# Filter_Board.net
KiCad netlist of a schematic drawn in EAGLE
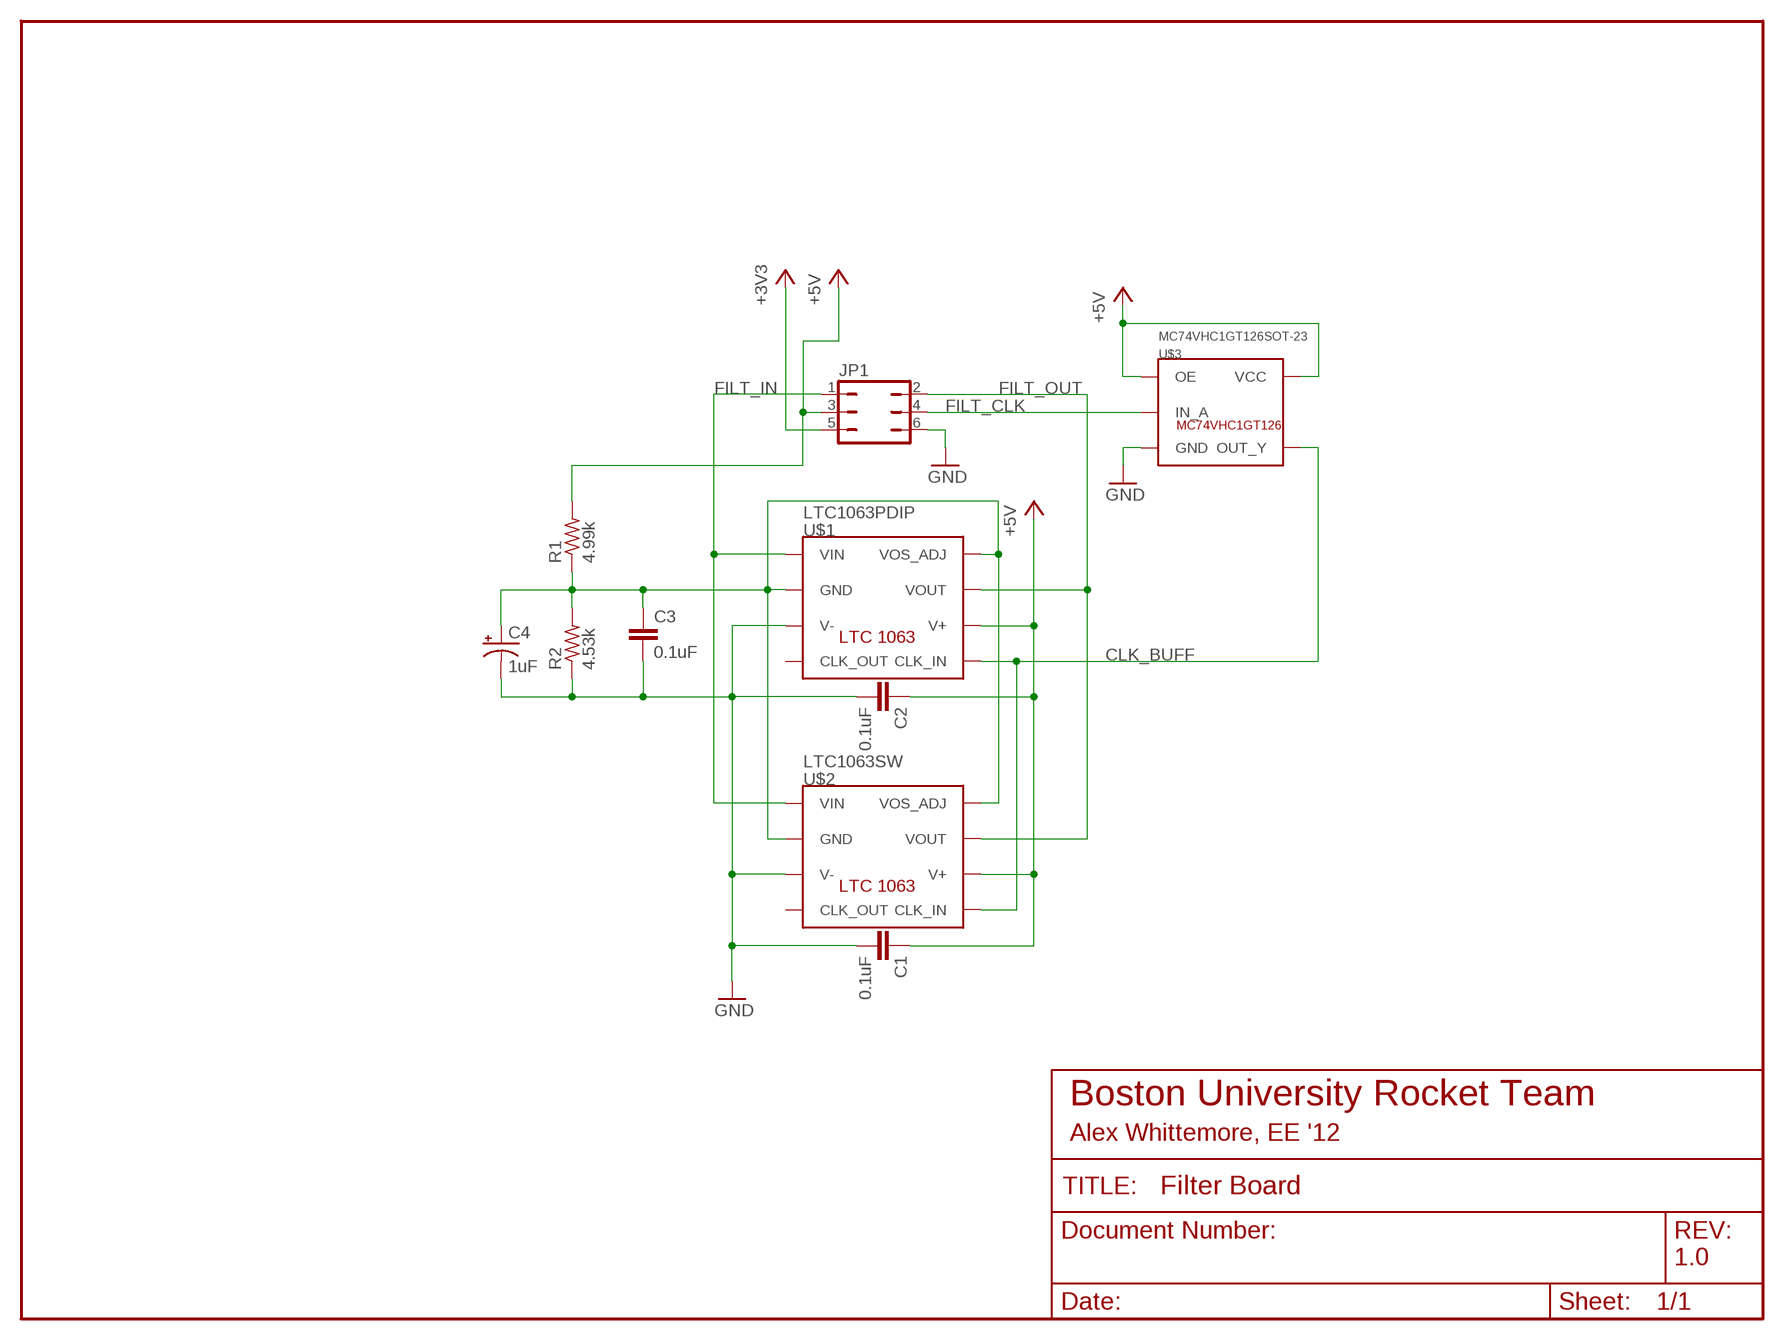
[diagram p0: schematic, sheet 1]

(export (version "E")
  (design (tool "Eeschema 10.0.6"))
  (components
    (comp (ref "C1")
      (value "0.1uF")
      (footprint "eagle-import:0402-CAP")
      (libsource (lib "eagle-import") (part "CAP0402-CAP"))
    )
    (comp (ref "C2")
      (value "0.1uF")
      (footprint "eagle-import:0402-CAP")
      (libsource (lib "eagle-import") (part "CAP0402-CAP"))
    )
    (comp (ref "C3")
      (value "0.1uF")
      (footprint "eagle-import:0402-CAP")
      (libsource (lib "eagle-import") (part "CAP0402-CAP"))
    )
    (comp (ref "C4")
      (value "1uF")
      (footprint "eagle-import:EIA3216")
      (libsource (lib "eagle-import") (part "CAP_POL1206"))
    )
    (comp (ref "JP1")
      (value "JP3Q")
      (footprint "eagle-import:JP3Q")
      (libsource (lib "eagle-import") (part "JP3Q"))
    )
    (comp (ref "R1")
      (value "4.99k")
      (footprint "eagle-import:0207_7")
      (libsource (lib "eagle-import") (part "R-US_0207/7"))
    )
    (comp (ref "R2")
      (value "4.53k")
      (footprint "eagle-import:0207_7")
      (libsource (lib "eagle-import") (part "R-US_0207/7"))
    )
    (comp (ref "U$1")
      (value "LTC1063PDIP")
      (footprint "eagle-import:SOCKED-08")
      (libsource (lib "eagle-import") (part "LTC1063PDIP"))
    )
    (comp (ref "U$2")
      (value "LTC1063SW")
      (footprint "eagle-import:SOP16")
      (libsource (lib "eagle-import") (part "LTC1063SW"))
    )
    (comp (ref "U$3")
      (value "MC74VHC1GT126SOT-23")
      (footprint "eagle-import:SOT23-5L")
      (libsource (lib "eagle-import") (part "MC74VHC1GT126SOT-23"))
    )
  )
  (nets
    (net (code "1") (name "+3V3") (class "Default")
      (node (ref "JP1") (pin "5") (pinfunction "5_5") (pintype "passive"))
    )
    (net (code "2") (name "+5V") (class "Default")
      (node (ref "C1") (pin "1") (pinfunction "1_1") (pintype "passive"))
      (node (ref "C2") (pin "1") (pinfunction "1_1") (pintype "passive"))
      (node (ref "JP1") (pin "3") (pinfunction "3_3") (pintype "passive"))
      (node (ref "R1") (pin "2") (pinfunction "2_2") (pintype "passive"))
      (node (ref "U$1") (pin "6") (pinfunction "V+_6") (pintype "bidirectional"))
      (node (ref "U$2") (pin "12") (pinfunction "V+_12") (pintype "bidirectional"))
      (node (ref "U$3") (pin "1") (pinfunction "OE_1") (pintype "bidirectional"))
      (node (ref "U$3") (pin "5") (pinfunction "VCC_5") (pintype "bidirectional"))
    )
    (net (code "3") (name "/CLK_BUFF") (class "Default")
      (node (ref "U$1") (pin "5") (pinfunction "CLK_IN_5") (pintype "bidirectional"))
      (node (ref "U$2") (pin "9") (pinfunction "CLK_IN_9") (pintype "bidirectional"))
      (node (ref "U$3") (pin "4") (pinfunction "OUT_Y_4") (pintype "bidirectional"))
    )
    (net (code "4") (name "/FILT_CLK") (class "Default")
      (node (ref "JP1") (pin "4") (pinfunction "4_4") (pintype "passive"))
      (node (ref "U$3") (pin "2") (pinfunction "IN_A_2") (pintype "bidirectional"))
    )
    (net (code "5") (name "/FILT_IN") (class "Default")
      (node (ref "JP1") (pin "1") (pinfunction "1_1") (pintype "passive"))
      (node (ref "U$1") (pin "1") (pinfunction "VIN_1") (pintype "bidirectional"))
      (node (ref "U$2") (pin "2") (pinfunction "VIN_2") (pintype "bidirectional"))
    )
    (net (code "6") (name "/FILT_OUT") (class "Default")
      (node (ref "JP1") (pin "2") (pinfunction "2_2") (pintype "passive"))
      (node (ref "U$1") (pin "7") (pinfunction "VOUT_7") (pintype "bidirectional"))
      (node (ref "U$2") (pin "14") (pinfunction "VOUT_14") (pintype "bidirectional"))
    )
    (net (code "7") (name "GND") (class "Default")
      (node (ref "C1") (pin "2") (pinfunction "2_2") (pintype "passive"))
      (node (ref "C2") (pin "2") (pinfunction "2_2") (pintype "passive"))
      (node (ref "C3") (pin "2") (pinfunction "2_2") (pintype "passive"))
      (node (ref "C4") (pin "C") (pinfunction "-_C") (pintype "passive"))
      (node (ref "JP1") (pin "6") (pinfunction "6_6") (pintype "passive"))
      (node (ref "R2") (pin "1") (pinfunction "1_1") (pintype "passive"))
      (node (ref "U$1") (pin "3") (pinfunction "V-_3") (pintype "bidirectional"))
      (node (ref "U$2") (pin "5") (pinfunction "V-_5") (pintype "bidirectional"))
      (node (ref "U$3") (pin "3") (pinfunction "GND_3") (pintype "bidirectional"))
    )
    (net (code "8") (name "Net-(C4-+)") (class "Default")
      (node (ref "C3") (pin "1") (pinfunction "1_1") (pintype "passive"))
      (node (ref "C4") (pin "A") (pinfunction "+_A") (pintype "passive"))
      (node (ref "R1") (pin "1") (pinfunction "1_1") (pintype "passive"))
      (node (ref "R2") (pin "2") (pinfunction "2_2") (pintype "passive"))
      (node (ref "U$1") (pin "2") (pinfunction "GND_2") (pintype "bidirectional"))
      (node (ref "U$1") (pin "8") (pinfunction "VOS_ADJ_8") (pintype "bidirectional"))
      (node (ref "U$2") (pin "16") (pinfunction "VOS_ADJ_16") (pintype "bidirectional"))
      (node (ref "U$2") (pin "3") (pinfunction "GND_3") (pintype "bidirectional"))
    )
    (net (code "9") (name "unconnected-(U$1-CLK_OUT-Pad4)") (class "Default")
      (node (ref "U$1") (pin "4") (pinfunction "CLK_OUT_4") (pintype "bidirectional"))
    )
    (net (code "10") (name "unconnected-(U$2-CLK_OUT-Pad8)") (class "Default")
      (node (ref "U$2") (pin "8") (pinfunction "CLK_OUT_8") (pintype "bidirectional"))
    )
  )
)
